# Sheet2.net
KiCad netlist of a schematic drawn in Altium Designer
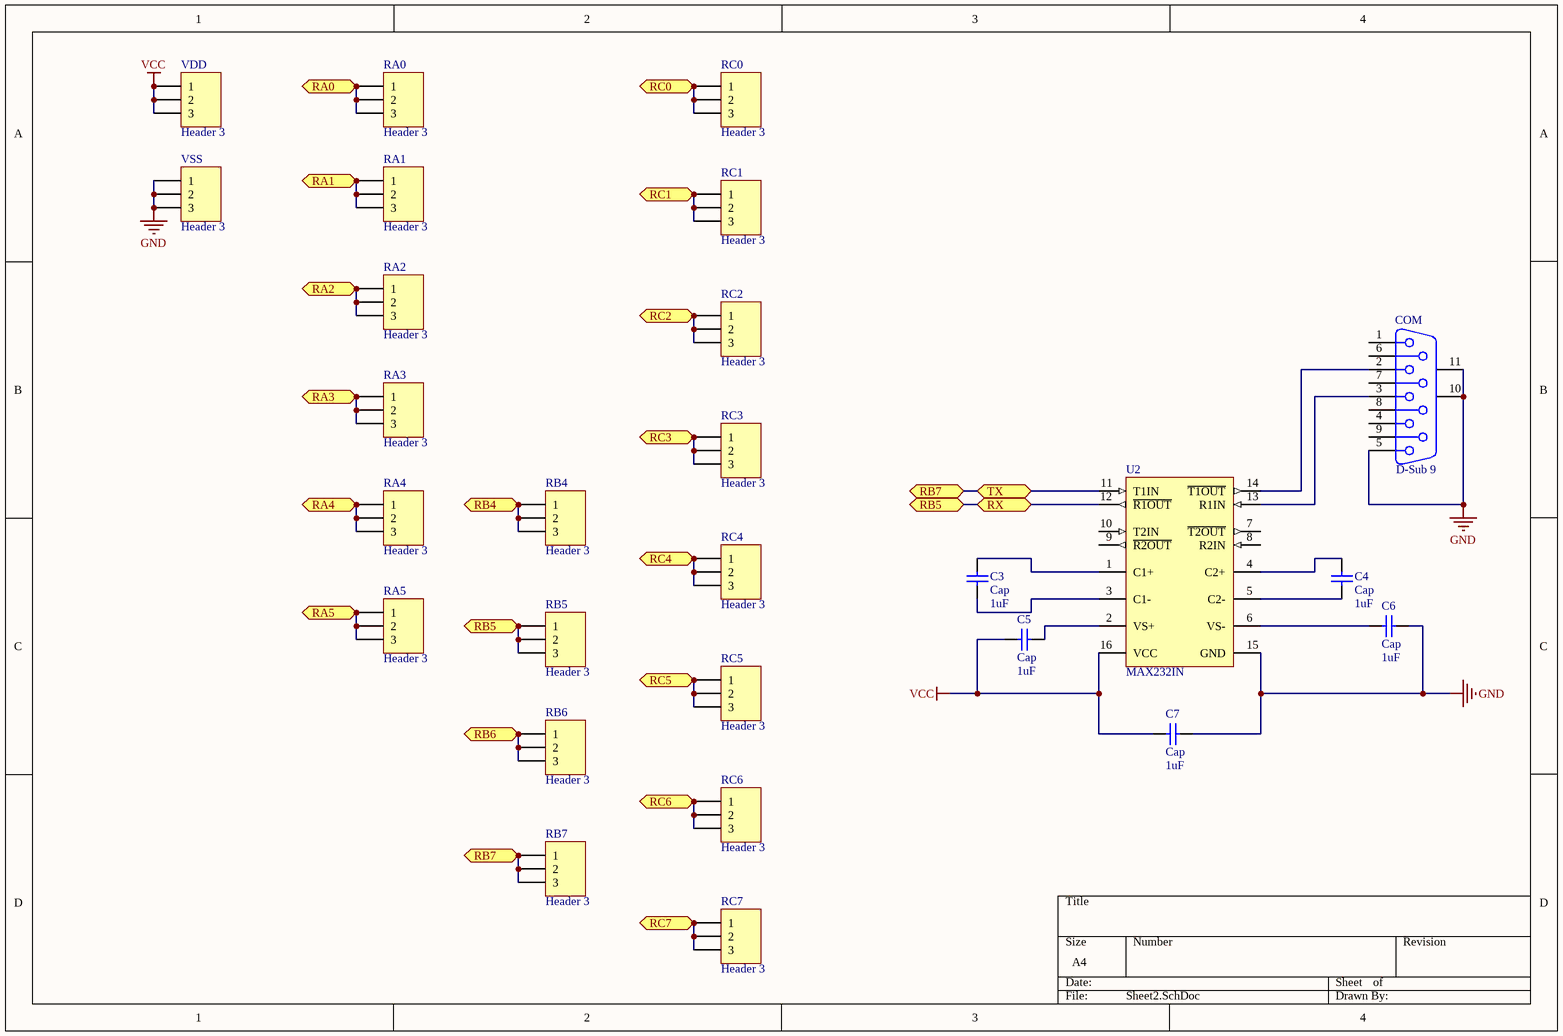
[diagram p0: Sheet2.SchDoc]

(export (version "E")
  (design (tool "Eeschema 10.0.6"))
  (components
    (comp (ref "C3")
      (value "Cap")
      (footprint "CAP-0.1")
      (description "Capacitor")
      (fields (field (name "ALTIUM_VALUE") "1uF") (field (name "PUBLISHER") "Altium Limited"))
      (libsource (lib "Miscellaneous Devices") (part "Cap"))
    )
    (comp (ref "C4")
      (value "Cap")
      (footprint "CAP-0.1")
      (description "Capacitor")
      (fields (field (name "ALTIUM_VALUE") "1uF") (field (name "PUBLISHER") "Altium Limited"))
      (libsource (lib "Miscellaneous Devices") (part "Cap"))
    )
    (comp (ref "C5")
      (value "Cap")
      (footprint "CAP-0.1")
      (description "Capacitor")
      (fields (field (name "ALTIUM_VALUE") "1uF") (field (name "PUBLISHER") "Altium Limited"))
      (libsource (lib "Miscellaneous Devices") (part "Cap"))
    )
    (comp (ref "C6")
      (value "Cap")
      (footprint "CAP-0.1")
      (description "Capacitor")
      (fields (field (name "ALTIUM_VALUE") "1uF") (field (name "PUBLISHER") "Altium Limited"))
      (libsource (lib "Miscellaneous Devices") (part "Cap"))
    )
    (comp (ref "C7")
      (value "Cap")
      (footprint "CAP-0.1")
      (description "Capacitor")
      (fields (field (name "ALTIUM_VALUE") "1uF") (field (name "PUBLISHER") "Altium Limited"))
      (libsource (lib "Miscellaneous Devices") (part "Cap"))
    )
    (comp (ref "COM")
      (value "D-Sub 9")
      (footprint "DSUB1.385-2H9")
      (description "Receptacle Assembly, 9 Position, Right Angle")
      (fields (field (name "PUBLISHER") "Altium Limited"))
      (libsource (lib "Miscellaneous Connectors") (part "D Connector 9"))
    )
    (comp (ref "RA0")
      (value "Header 3")
      (footprint "HDR1X3")
      (description "Header, 3-Pin")
      (fields (field (name "PUBLISHER") "Altium Limited"))
      (libsource (lib "Miscellaneous Connectors") (part "Header 3"))
    )
    (comp (ref "RA1")
      (value "Header 3")
      (footprint "HDR1X3")
      (description "Header, 3-Pin")
      (fields (field (name "PUBLISHER") "Altium Limited"))
      (libsource (lib "Miscellaneous Connectors") (part "Header 3"))
    )
    (comp (ref "RA2")
      (value "Header 3")
      (footprint "HDR1X3")
      (description "Header, 3-Pin")
      (fields (field (name "PUBLISHER") "Altium Limited"))
      (libsource (lib "Miscellaneous Connectors") (part "Header 3"))
    )
    (comp (ref "RA3")
      (value "Header 3")
      (footprint "HDR1X3")
      (description "Header, 3-Pin")
      (fields (field (name "PUBLISHER") "Altium Limited"))
      (libsource (lib "Miscellaneous Connectors") (part "Header 3"))
    )
    (comp (ref "RA4")
      (value "Header 3")
      (footprint "HDR1X3")
      (description "Header, 3-Pin")
      (fields (field (name "PUBLISHER") "Altium Limited"))
      (libsource (lib "Miscellaneous Connectors") (part "Header 3"))
    )
    (comp (ref "RA5")
      (value "Header 3")
      (footprint "HDR1X3")
      (description "Header, 3-Pin")
      (fields (field (name "PUBLISHER") "Altium Limited"))
      (libsource (lib "Miscellaneous Connectors") (part "Header 3"))
    )
    (comp (ref "RB4")
      (value "Header 3")
      (footprint "HDR1X3")
      (description "Header, 3-Pin")
      (fields (field (name "PUBLISHER") "Altium Limited"))
      (libsource (lib "Miscellaneous Connectors") (part "Header 3"))
    )
    (comp (ref "RB5")
      (value "Header 3")
      (footprint "HDR1X3")
      (description "Header, 3-Pin")
      (fields (field (name "PUBLISHER") "Altium Limited"))
      (libsource (lib "Miscellaneous Connectors") (part "Header 3"))
    )
    (comp (ref "RB6")
      (value "Header 3")
      (footprint "HDR1X3")
      (description "Header, 3-Pin")
      (fields (field (name "PUBLISHER") "Altium Limited"))
      (libsource (lib "Miscellaneous Connectors") (part "Header 3"))
    )
    (comp (ref "RB7")
      (value "Header 3")
      (footprint "HDR1X3")
      (description "Header, 3-Pin")
      (fields (field (name "PUBLISHER") "Altium Limited"))
      (libsource (lib "Miscellaneous Connectors") (part "Header 3"))
    )
    (comp (ref "RC0")
      (value "Header 3")
      (footprint "HDR1X3")
      (description "Header, 3-Pin")
      (fields (field (name "PUBLISHER") "Altium Limited"))
      (libsource (lib "Miscellaneous Connectors") (part "Header 3"))
    )
    (comp (ref "RC1")
      (value "Header 3")
      (footprint "HDR1X3")
      (description "Header, 3-Pin")
      (fields (field (name "PUBLISHER") "Altium Limited"))
      (libsource (lib "Miscellaneous Connectors") (part "Header 3"))
    )
    (comp (ref "RC2")
      (value "Header 3")
      (footprint "HDR1X3")
      (description "Header, 3-Pin")
      (fields (field (name "PUBLISHER") "Altium Limited"))
      (libsource (lib "Miscellaneous Connectors") (part "Header 3"))
    )
    (comp (ref "RC3")
      (value "Header 3")
      (footprint "HDR1X3")
      (description "Header, 3-Pin")
      (fields (field (name "PUBLISHER") "Altium Limited"))
      (libsource (lib "Miscellaneous Connectors") (part "Header 3"))
    )
    (comp (ref "RC4")
      (value "Header 3")
      (footprint "HDR1X3")
      (description "Header, 3-Pin")
      (fields (field (name "PUBLISHER") "Altium Limited"))
      (libsource (lib "Miscellaneous Connectors") (part "Header 3"))
    )
    (comp (ref "RC5")
      (value "Header 3")
      (footprint "HDR1X3")
      (description "Header, 3-Pin")
      (fields (field (name "PUBLISHER") "Altium Limited"))
      (libsource (lib "Miscellaneous Connectors") (part "Header 3"))
    )
    (comp (ref "RC6")
      (value "Header 3")
      (footprint "HDR1X3")
      (description "Header, 3-Pin")
      (fields (field (name "PUBLISHER") "Altium Limited"))
      (libsource (lib "Miscellaneous Connectors") (part "Header 3"))
    )
    (comp (ref "RC7")
      (value "Header 3")
      (footprint "HDR1X3")
      (description "Header, 3-Pin")
      (fields (field (name "PUBLISHER") "Altium Limited"))
      (libsource (lib "Miscellaneous Connectors") (part "Header 3"))
    )
    (comp (ref "U2")
      (value "MAX232IN")
      (footprint "N0016A")
      (description "Dual EIA-232 Driver / Receiver, -40 to 85 degC, 16-Pin PDIP (N), Pb-Free (RoHS)")
      (libsource (lib "Altium Content Vault") (part "CMP-0299-00077-2"))
    )
    (comp (ref "VDD")
      (value "Header 3")
      (footprint "HDR1X3")
      (description "Header, 3-Pin")
      (fields (field (name "PUBLISHER") "Altium Limited"))
      (libsource (lib "Miscellaneous Connectors") (part "Header 3"))
    )
    (comp (ref "VSS")
      (value "Header 3")
      (footprint "HDR1X3")
      (description "Header, 3-Pin")
      (fields (field (name "PUBLISHER") "Altium Limited"))
      (libsource (lib "Miscellaneous Connectors") (part "Header 3"))
    )
  )
  (nets
    (net (code "1") (name "/RA0") (class "Default")
      (node (ref "RA0") (pin "1") (pinfunction "1_1") (pintype "passive"))
      (node (ref "RA0") (pin "2") (pinfunction "2_2") (pintype "passive"))
      (node (ref "RA0") (pin "3") (pinfunction "3_3") (pintype "passive"))
    )
    (net (code "2") (name "/RA1") (class "Default")
      (node (ref "RA1") (pin "1") (pinfunction "1_1") (pintype "passive"))
      (node (ref "RA1") (pin "2") (pinfunction "2_2") (pintype "passive"))
      (node (ref "RA1") (pin "3") (pinfunction "3_3") (pintype "passive"))
    )
    (net (code "3") (name "/RA2") (class "Default")
      (node (ref "RA2") (pin "1") (pinfunction "1_1") (pintype "passive"))
      (node (ref "RA2") (pin "2") (pinfunction "2_2") (pintype "passive"))
      (node (ref "RA2") (pin "3") (pinfunction "3_3") (pintype "passive"))
    )
    (net (code "4") (name "/RA3") (class "Default")
      (node (ref "RA3") (pin "1") (pinfunction "1_1") (pintype "passive"))
      (node (ref "RA3") (pin "2") (pinfunction "2_2") (pintype "passive"))
      (node (ref "RA3") (pin "3") (pinfunction "3_3") (pintype "passive"))
    )
    (net (code "5") (name "/RA4") (class "Default")
      (node (ref "RA4") (pin "1") (pinfunction "1_1") (pintype "passive"))
      (node (ref "RA4") (pin "2") (pinfunction "2_2") (pintype "passive"))
      (node (ref "RA4") (pin "3") (pinfunction "3_3") (pintype "passive"))
    )
    (net (code "6") (name "/RA5") (class "Default")
      (node (ref "RA5") (pin "1") (pinfunction "1_1") (pintype "passive"))
      (node (ref "RA5") (pin "2") (pinfunction "2_2") (pintype "passive"))
      (node (ref "RA5") (pin "3") (pinfunction "3_3") (pintype "passive"))
    )
    (net (code "7") (name "/RB4") (class "Default")
      (node (ref "RB4") (pin "1") (pinfunction "1_1") (pintype "passive"))
      (node (ref "RB4") (pin "2") (pinfunction "2_2") (pintype "passive"))
      (node (ref "RB4") (pin "3") (pinfunction "3_3") (pintype "passive"))
    )
    (net (code "8") (name "/RB5") (class "Default")
      (node (ref "RB5") (pin "1") (pinfunction "1_1") (pintype "passive"))
      (node (ref "RB5") (pin "2") (pinfunction "2_2") (pintype "passive"))
      (node (ref "RB5") (pin "3") (pinfunction "3_3") (pintype "passive"))
      (node (ref "U2") (pin "12") (pinfunction "~{R1OUT}_12") (pintype "output"))
    )
    (net (code "9") (name "/RB6") (class "Default")
      (node (ref "RB6") (pin "1") (pinfunction "1_1") (pintype "passive"))
      (node (ref "RB6") (pin "2") (pinfunction "2_2") (pintype "passive"))
      (node (ref "RB6") (pin "3") (pinfunction "3_3") (pintype "passive"))
    )
    (net (code "10") (name "/RB7") (class "Default")
      (node (ref "RB7") (pin "1") (pinfunction "1_1") (pintype "passive"))
      (node (ref "RB7") (pin "2") (pinfunction "2_2") (pintype "passive"))
      (node (ref "RB7") (pin "3") (pinfunction "3_3") (pintype "passive"))
      (node (ref "U2") (pin "11") (pinfunction "T1IN_11") (pintype "input"))
    )
    (net (code "11") (name "/RC0") (class "Default")
      (node (ref "RC0") (pin "1") (pinfunction "1_1") (pintype "passive"))
      (node (ref "RC0") (pin "2") (pinfunction "2_2") (pintype "passive"))
      (node (ref "RC0") (pin "3") (pinfunction "3_3") (pintype "passive"))
    )
    (net (code "12") (name "/RC1") (class "Default")
      (node (ref "RC1") (pin "1") (pinfunction "1_1") (pintype "passive"))
      (node (ref "RC1") (pin "2") (pinfunction "2_2") (pintype "passive"))
      (node (ref "RC1") (pin "3") (pinfunction "3_3") (pintype "passive"))
    )
    (net (code "13") (name "/RC2") (class "Default")
      (node (ref "RC2") (pin "1") (pinfunction "1_1") (pintype "passive"))
      (node (ref "RC2") (pin "2") (pinfunction "2_2") (pintype "passive"))
      (node (ref "RC2") (pin "3") (pinfunction "3_3") (pintype "passive"))
    )
    (net (code "14") (name "/RC3") (class "Default")
      (node (ref "RC3") (pin "1") (pinfunction "1_1") (pintype "passive"))
      (node (ref "RC3") (pin "2") (pinfunction "2_2") (pintype "passive"))
      (node (ref "RC3") (pin "3") (pinfunction "3_3") (pintype "passive"))
    )
    (net (code "15") (name "/RC4") (class "Default")
      (node (ref "RC4") (pin "1") (pinfunction "1_1") (pintype "passive"))
      (node (ref "RC4") (pin "2") (pinfunction "2_2") (pintype "passive"))
      (node (ref "RC4") (pin "3") (pinfunction "3_3") (pintype "passive"))
    )
    (net (code "16") (name "/RC5") (class "Default")
      (node (ref "RC5") (pin "1") (pinfunction "1_1") (pintype "passive"))
      (node (ref "RC5") (pin "2") (pinfunction "2_2") (pintype "passive"))
      (node (ref "RC5") (pin "3") (pinfunction "3_3") (pintype "passive"))
    )
    (net (code "17") (name "/RC6") (class "Default")
      (node (ref "RC6") (pin "1") (pinfunction "1_1") (pintype "passive"))
      (node (ref "RC6") (pin "2") (pinfunction "2_2") (pintype "passive"))
      (node (ref "RC6") (pin "3") (pinfunction "3_3") (pintype "passive"))
    )
    (net (code "18") (name "/RC7") (class "Default")
      (node (ref "RC7") (pin "1") (pinfunction "1_1") (pintype "passive"))
      (node (ref "RC7") (pin "2") (pinfunction "2_2") (pintype "passive"))
      (node (ref "RC7") (pin "3") (pinfunction "3_3") (pintype "passive"))
    )
    (net (code "19") (name "GND") (class "Default")
      (node (ref "C6") (pin "2") (pinfunction "2_2") (pintype "passive"))
      (node (ref "C7") (pin "2") (pinfunction "2_2") (pintype "passive"))
      (node (ref "COM") (pin "10") (pinfunction "MH1_10") (pintype "passive"))
      (node (ref "COM") (pin "11") (pinfunction "MH2_11") (pintype "passive"))
      (node (ref "COM") (pin "5") (pinfunction "5_5") (pintype "passive"))
      (node (ref "U2") (pin "15") (pinfunction "GND_15") (pintype "power_in"))
      (node (ref "VSS") (pin "1") (pinfunction "1_1") (pintype "passive"))
      (node (ref "VSS") (pin "2") (pinfunction "2_2") (pintype "passive"))
      (node (ref "VSS") (pin "3") (pinfunction "3_3") (pintype "passive"))
    )
    (net (code "20") (name "Net-(U2-C1+)") (class "Default")
      (node (ref "C3") (pin "1") (pinfunction "1_1") (pintype "passive"))
      (node (ref "U2") (pin "1") (pinfunction "C1+_1") (pintype "passive"))
    )
    (net (code "21") (name "Net-(U2-C1-)") (class "Default")
      (node (ref "C3") (pin "2") (pinfunction "2_2") (pintype "passive"))
      (node (ref "U2") (pin "3") (pinfunction "C1-_3") (pintype "passive"))
    )
    (net (code "22") (name "Net-(U2-C2+)") (class "Default")
      (node (ref "C4") (pin "1") (pinfunction "1_1") (pintype "passive"))
      (node (ref "U2") (pin "4") (pinfunction "C2+_4") (pintype "passive"))
    )
    (net (code "23") (name "Net-(U2-C2-)") (class "Default")
      (node (ref "C4") (pin "2") (pinfunction "2_2") (pintype "passive"))
      (node (ref "U2") (pin "5") (pinfunction "C2-_5") (pintype "passive"))
    )
    (net (code "24") (name "Net-(U2-R1IN)") (class "Default")
      (node (ref "COM") (pin "3") (pinfunction "3_3") (pintype "passive"))
      (node (ref "U2") (pin "13") (pinfunction "R1IN_13") (pintype "input"))
    )
    (net (code "25") (name "Net-(U2-VS+)") (class "Default")
      (node (ref "C5") (pin "2") (pinfunction "2_2") (pintype "passive"))
      (node (ref "U2") (pin "2") (pinfunction "VS+_2") (pintype "power_in"))
    )
    (net (code "26") (name "Net-(U2-VS-)") (class "Default")
      (node (ref "C6") (pin "1") (pinfunction "1_1") (pintype "passive"))
      (node (ref "U2") (pin "6") (pinfunction "VS-_6") (pintype "power_in"))
    )
    (net (code "27") (name "Net-(U2-~{T1OUT})") (class "Default")
      (node (ref "COM") (pin "2") (pinfunction "2_2") (pintype "passive"))
      (node (ref "U2") (pin "14") (pinfunction "~{T1OUT}_14") (pintype "output"))
    )
    (net (code "28") (name "VCC") (class "Default")
      (node (ref "C5") (pin "1") (pinfunction "1_1") (pintype "passive"))
      (node (ref "C7") (pin "1") (pinfunction "1_1") (pintype "passive"))
      (node (ref "U2") (pin "16") (pinfunction "VCC_16") (pintype "power_in"))
      (node (ref "VDD") (pin "1") (pinfunction "1_1") (pintype "passive"))
      (node (ref "VDD") (pin "2") (pinfunction "2_2") (pintype "passive"))
      (node (ref "VDD") (pin "3") (pinfunction "3_3") (pintype "passive"))
    )
    (net (code "29") (name "unconnected-(COM-Pad1)") (class "Default")
      (node (ref "COM") (pin "1") (pinfunction "1_1") (pintype "passive"))
    )
    (net (code "30") (name "unconnected-(COM-Pad4)") (class "Default")
      (node (ref "COM") (pin "4") (pinfunction "4_4") (pintype "passive"))
    )
    (net (code "31") (name "unconnected-(COM-Pad6)") (class "Default")
      (node (ref "COM") (pin "6") (pinfunction "6_6") (pintype "passive"))
    )
    (net (code "32") (name "unconnected-(COM-Pad7)") (class "Default")
      (node (ref "COM") (pin "7") (pinfunction "7_7") (pintype "passive"))
    )
    (net (code "33") (name "unconnected-(COM-Pad8)") (class "Default")
      (node (ref "COM") (pin "8") (pinfunction "8_8") (pintype "passive"))
    )
    (net (code "34") (name "unconnected-(COM-Pad9)") (class "Default")
      (node (ref "COM") (pin "9") (pinfunction "9_9") (pintype "passive"))
    )
    (net (code "35") (name "unconnected-(U2-R2IN-Pad8)") (class "Default")
      (node (ref "U2") (pin "8") (pinfunction "R2IN_8") (pintype "input"))
    )
    (net (code "36") (name "unconnected-(U2-T2IN-Pad10)") (class "Default")
      (node (ref "U2") (pin "10") (pinfunction "T2IN_10") (pintype "input"))
    )
    (net (code "37") (name "unconnected-(U2-~{R2OUT}-Pad9)") (class "Default")
      (node (ref "U2") (pin "9") (pinfunction "~{R2OUT}_9") (pintype "output"))
    )
    (net (code "38") (name "unconnected-(U2-~{T2OUT}-Pad7)") (class "Default")
      (node (ref "U2") (pin "7") (pinfunction "~{T2OUT}_7") (pintype "output"))
    )
  )
)
